# ace128_pcf8574_smd_v3.net
KiCad netlist of a schematic drawn in EAGLE
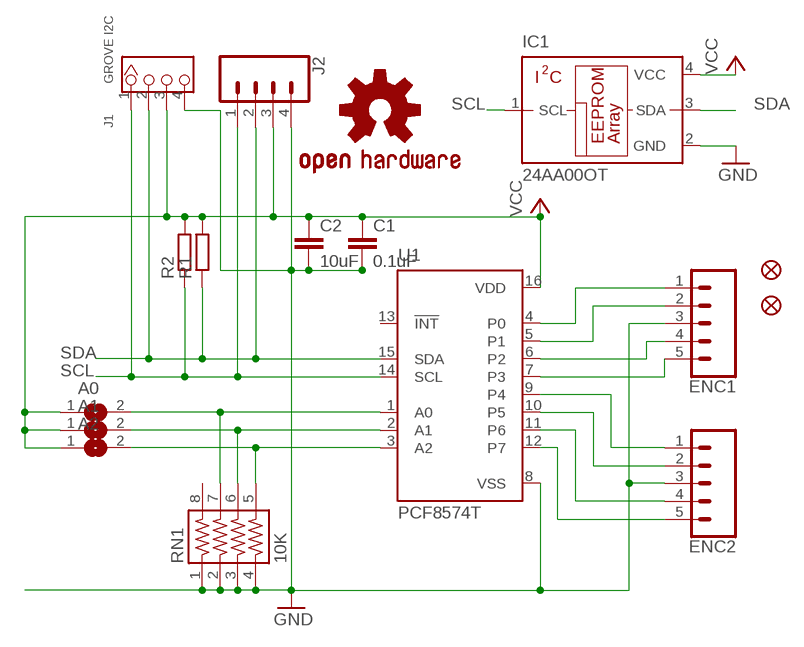
[diagram p0: schematic, sheet 1]

(export (version "E")
  (design (tool "Eeschema 10.0.6"))
  (components
    (comp (ref "A0") (value "SJ") (footprint "eagle-import:SJ") (libsource (lib "eagle-import") (part "SJ")))
    (comp (ref "A1") (value "SJ") (footprint "eagle-import:SJ") (libsource (lib "eagle-import") (part "SJ")))
    (comp (ref "A2") (value "SJ") (footprint "eagle-import:SJ") (libsource (lib "eagle-import") (part "SJ")))
    (comp (ref "C1")
      (value "0.1uF")
      (footprint "eagle-import:C0603")
      (libsource (lib "eagle-import") (part "rcl_334_C-EUC0603"))
    )
    (comp (ref "C2")
      (value "10uF")
      (footprint "eagle-import:C0805")
      (libsource (lib "eagle-import") (part "C-EUC0805"))
    )
    (comp (ref "ENC1")
      (value "CONN_05")
      (footprint "eagle-import:1X05")
      (libsource (lib "eagle-import") (part "CONN_05"))
    )
    (comp (ref "ENC2")
      (value "CONN_05")
      (footprint "eagle-import:1X05")
      (libsource (lib "eagle-import") (part "CONN_05"))
    )
    (comp (ref "FD1")
      (value "FIDUCIAL1X2")
      (footprint "eagle-import:FIDUCIAL-1X2")
      (libsource (lib "eagle-import") (part "FIDUCIAL1X2"))
    )
    (comp (ref "FD2")
      (value "FIDUCIAL1X2")
      (footprint "eagle-import:FIDUCIAL-1X2")
      (libsource (lib "eagle-import") (part "FIDUCIAL1X2"))
    )
    (comp (ref "IC1")
      (value "24AA00OT")
      (footprint "eagle-import:SOT23-5L")
      (fields (field (name "MF") "MICROCHIP") (field (name "MPN") "24AA00T-I/OTG"))
      (libsource (lib "eagle-import") (part "2400OTAA"))
    )
    (comp (ref "J1")
      (value "GROVE I2C")
      (footprint "eagle-import:HW4-2.0")
      (libsource (lib "eagle-import") (part "GROVE-CONNECTOR-DIP(4P-2.0)"))
    )
    (comp (ref "J2")
      (value "CONN_04")
      (footprint "eagle-import:1X04")
      (libsource (lib "eagle-import") (part "CONN_04"))
    )
    (comp (ref "LOGO1")
      (value "OSHW-LOGOS")
      (footprint "eagle-import:OSHW-LOGO-S")
      (libsource (lib "eagle-import") (part "OSHW-LOGOS"))
    )
    (comp (ref "R1")
      (value "R-EU_0207/2V")
      (footprint "eagle-import:0207_2V")
      (libsource (lib "eagle-import") (part "R-EU_0207/2V"))
    )
    (comp (ref "R2")
      (value "R-EU_0207/2V")
      (footprint "eagle-import:0207_2V")
      (libsource (lib "eagle-import") (part "R-EU_0207/2V"))
    )
    (comp (ref "RN1")
      (value "10K")
      (footprint "eagle-import:743-8")
      (libsource (lib "eagle-import") (part "743-8"))
    )
    (comp (ref "U1")
      (value "PCF8574T")
      (footprint "eagle-import:SO16W")
      (fields (field (name "MPN") "PCF8574T/3,512"))
      (libsource (lib "eagle-import") (part "PCF8574T"))
    )
  )
  (nets
    (net (code "1") (name "/SCL") (class "Default")
      (node (ref "IC1") (pin "1") (pinfunction "SCL_1") (pintype "input"))
      (node (ref "J1") (pin "1") (pinfunction "1_1") (pintype "bidirectional"))
      (node (ref "J2") (pin "1") (pinfunction "1_1") (pintype "passive"))
      (node (ref "R2") (pin "1") (pinfunction "1_1") (pintype "passive"))
      (node (ref "U1") (pin "14") (pinfunction "SCL_14") (pintype "input"))
    )
    (net (code "2") (name "/SDA") (class "Default")
      (node (ref "IC1") (pin "3") (pinfunction "SDA_3") (pintype "bidirectional"))
      (node (ref "J1") (pin "2") (pinfunction "2_2") (pintype "bidirectional"))
      (node (ref "J2") (pin "2") (pinfunction "2_2") (pintype "passive"))
      (node (ref "R1") (pin "1") (pinfunction "1_1") (pintype "passive"))
      (node (ref "U1") (pin "15") (pinfunction "SDA_15") (pintype "bidirectional"))
    )
    (net (code "3") (name "GND") (class "Default")
      (node (ref "C1") (pin "2") (pinfunction "2_2") (pintype "passive"))
      (node (ref "C2") (pin "2") (pinfunction "2_2") (pintype "passive"))
      (node (ref "ENC1") (pin "3") (pinfunction "3_3") (pintype "passive"))
      (node (ref "ENC2") (pin "3") (pinfunction "3_3") (pintype "passive"))
      (node (ref "IC1") (pin "2") (pinfunction "GND_2") (pintype "power_in"))
      (node (ref "J1") (pin "4") (pinfunction "4_4") (pintype "bidirectional"))
      (node (ref "J2") (pin "4") (pinfunction "4_4") (pintype "passive"))
      (node (ref "RN1") (pin "1") (pinfunction "1_1") (pintype "passive"))
      (node (ref "RN1") (pin "2") (pinfunction "2_2") (pintype "passive"))
      (node (ref "RN1") (pin "3") (pinfunction "3_3") (pintype "passive"))
      (node (ref "RN1") (pin "4") (pinfunction "4_4") (pintype "passive"))
      (node (ref "U1") (pin "8") (pinfunction "VSS_8") (pintype "power_in"))
    )
    (net (code "4") (name "Net-(U1-A0)") (class "Default")
      (node (ref "A0") (pin "2") (pinfunction "2_2") (pintype "passive"))
      (node (ref "RN1") (pin "7") (pinfunction "7_7") (pintype "passive"))
      (node (ref "U1") (pin "1") (pinfunction "A0_1") (pintype "input"))
    )
    (net (code "5") (name "Net-(U1-A1)") (class "Default")
      (node (ref "A1") (pin "2") (pinfunction "2_2") (pintype "passive"))
      (node (ref "RN1") (pin "6") (pinfunction "6_6") (pintype "passive"))
      (node (ref "U1") (pin "2") (pinfunction "A1_2") (pintype "input"))
    )
    (net (code "6") (name "Net-(U1-A2)") (class "Default")
      (node (ref "A2") (pin "2") (pinfunction "2_2") (pintype "passive"))
      (node (ref "RN1") (pin "5") (pinfunction "5_5") (pintype "passive"))
      (node (ref "U1") (pin "3") (pinfunction "A2_3") (pintype "input"))
    )
    (net (code "7") (name "Net-(U1-P0)") (class "Default")
      (node (ref "ENC1") (pin "1") (pinfunction "1_1") (pintype "passive"))
      (node (ref "U1") (pin "4") (pinfunction "P0_4") (pintype "bidirectional"))
    )
    (net (code "8") (name "Net-(U1-P1)") (class "Default")
      (node (ref "ENC1") (pin "2") (pinfunction "2_2") (pintype "passive"))
      (node (ref "U1") (pin "5") (pinfunction "P1_5") (pintype "bidirectional"))
    )
    (net (code "9") (name "Net-(U1-P2)") (class "Default")
      (node (ref "ENC1") (pin "4") (pinfunction "4_4") (pintype "passive"))
      (node (ref "U1") (pin "6") (pinfunction "P2_6") (pintype "bidirectional"))
    )
    (net (code "10") (name "Net-(U1-P3)") (class "Default")
      (node (ref "ENC1") (pin "5") (pinfunction "5_5") (pintype "passive"))
      (node (ref "U1") (pin "7") (pinfunction "P3_7") (pintype "bidirectional"))
    )
    (net (code "11") (name "Net-(U1-P4)") (class "Default")
      (node (ref "ENC2") (pin "1") (pinfunction "1_1") (pintype "passive"))
      (node (ref "U1") (pin "9") (pinfunction "P4_9") (pintype "bidirectional"))
    )
    (net (code "12") (name "Net-(U1-P5)") (class "Default")
      (node (ref "ENC2") (pin "2") (pinfunction "2_2") (pintype "passive"))
      (node (ref "U1") (pin "10") (pinfunction "P5_10") (pintype "bidirectional"))
    )
    (net (code "13") (name "Net-(U1-P6)") (class "Default")
      (node (ref "ENC2") (pin "4") (pinfunction "4_4") (pintype "passive"))
      (node (ref "U1") (pin "11") (pinfunction "P6_11") (pintype "bidirectional"))
    )
    (net (code "14") (name "Net-(U1-P7)") (class "Default")
      (node (ref "ENC2") (pin "5") (pinfunction "5_5") (pintype "passive"))
      (node (ref "U1") (pin "12") (pinfunction "P7_12") (pintype "bidirectional"))
    )
    (net (code "15") (name "VCC") (class "Default")
      (node (ref "A0") (pin "1") (pinfunction "1_1") (pintype "passive"))
      (node (ref "A1") (pin "1") (pinfunction "1_1") (pintype "passive"))
      (node (ref "A2") (pin "1") (pinfunction "1_1") (pintype "passive"))
      (node (ref "C1") (pin "1") (pinfunction "1_1") (pintype "passive"))
      (node (ref "C2") (pin "1") (pinfunction "1_1") (pintype "passive"))
      (node (ref "IC1") (pin "4") (pinfunction "VCC_4") (pintype "power_in"))
      (node (ref "J1") (pin "3") (pinfunction "3_3") (pintype "bidirectional"))
      (node (ref "J2") (pin "3") (pinfunction "3_3") (pintype "passive"))
      (node (ref "R1") (pin "2") (pinfunction "2_2") (pintype "passive"))
      (node (ref "R2") (pin "2") (pinfunction "2_2") (pintype "passive"))
      (node (ref "U1") (pin "16") (pinfunction "VDD_16") (pintype "power_in"))
    )
    (net (code "16") (name "unconnected-(RN1-Pad8)") (class "Default")
      (node (ref "RN1") (pin "8") (pinfunction "8_8") (pintype "passive"))
    )
    (net (code "17") (name "unconnected-(U1-~{INT}-Pad13)") (class "Default")
      (node (ref "U1") (pin "13") (pinfunction "~{INT}_13") (pintype "output"))
    )
  )
)
